# SCH_AGV_genzero_10_ir_array_2024-06-24.net
KiCad netlist of a schematic drawn in EasyEDA
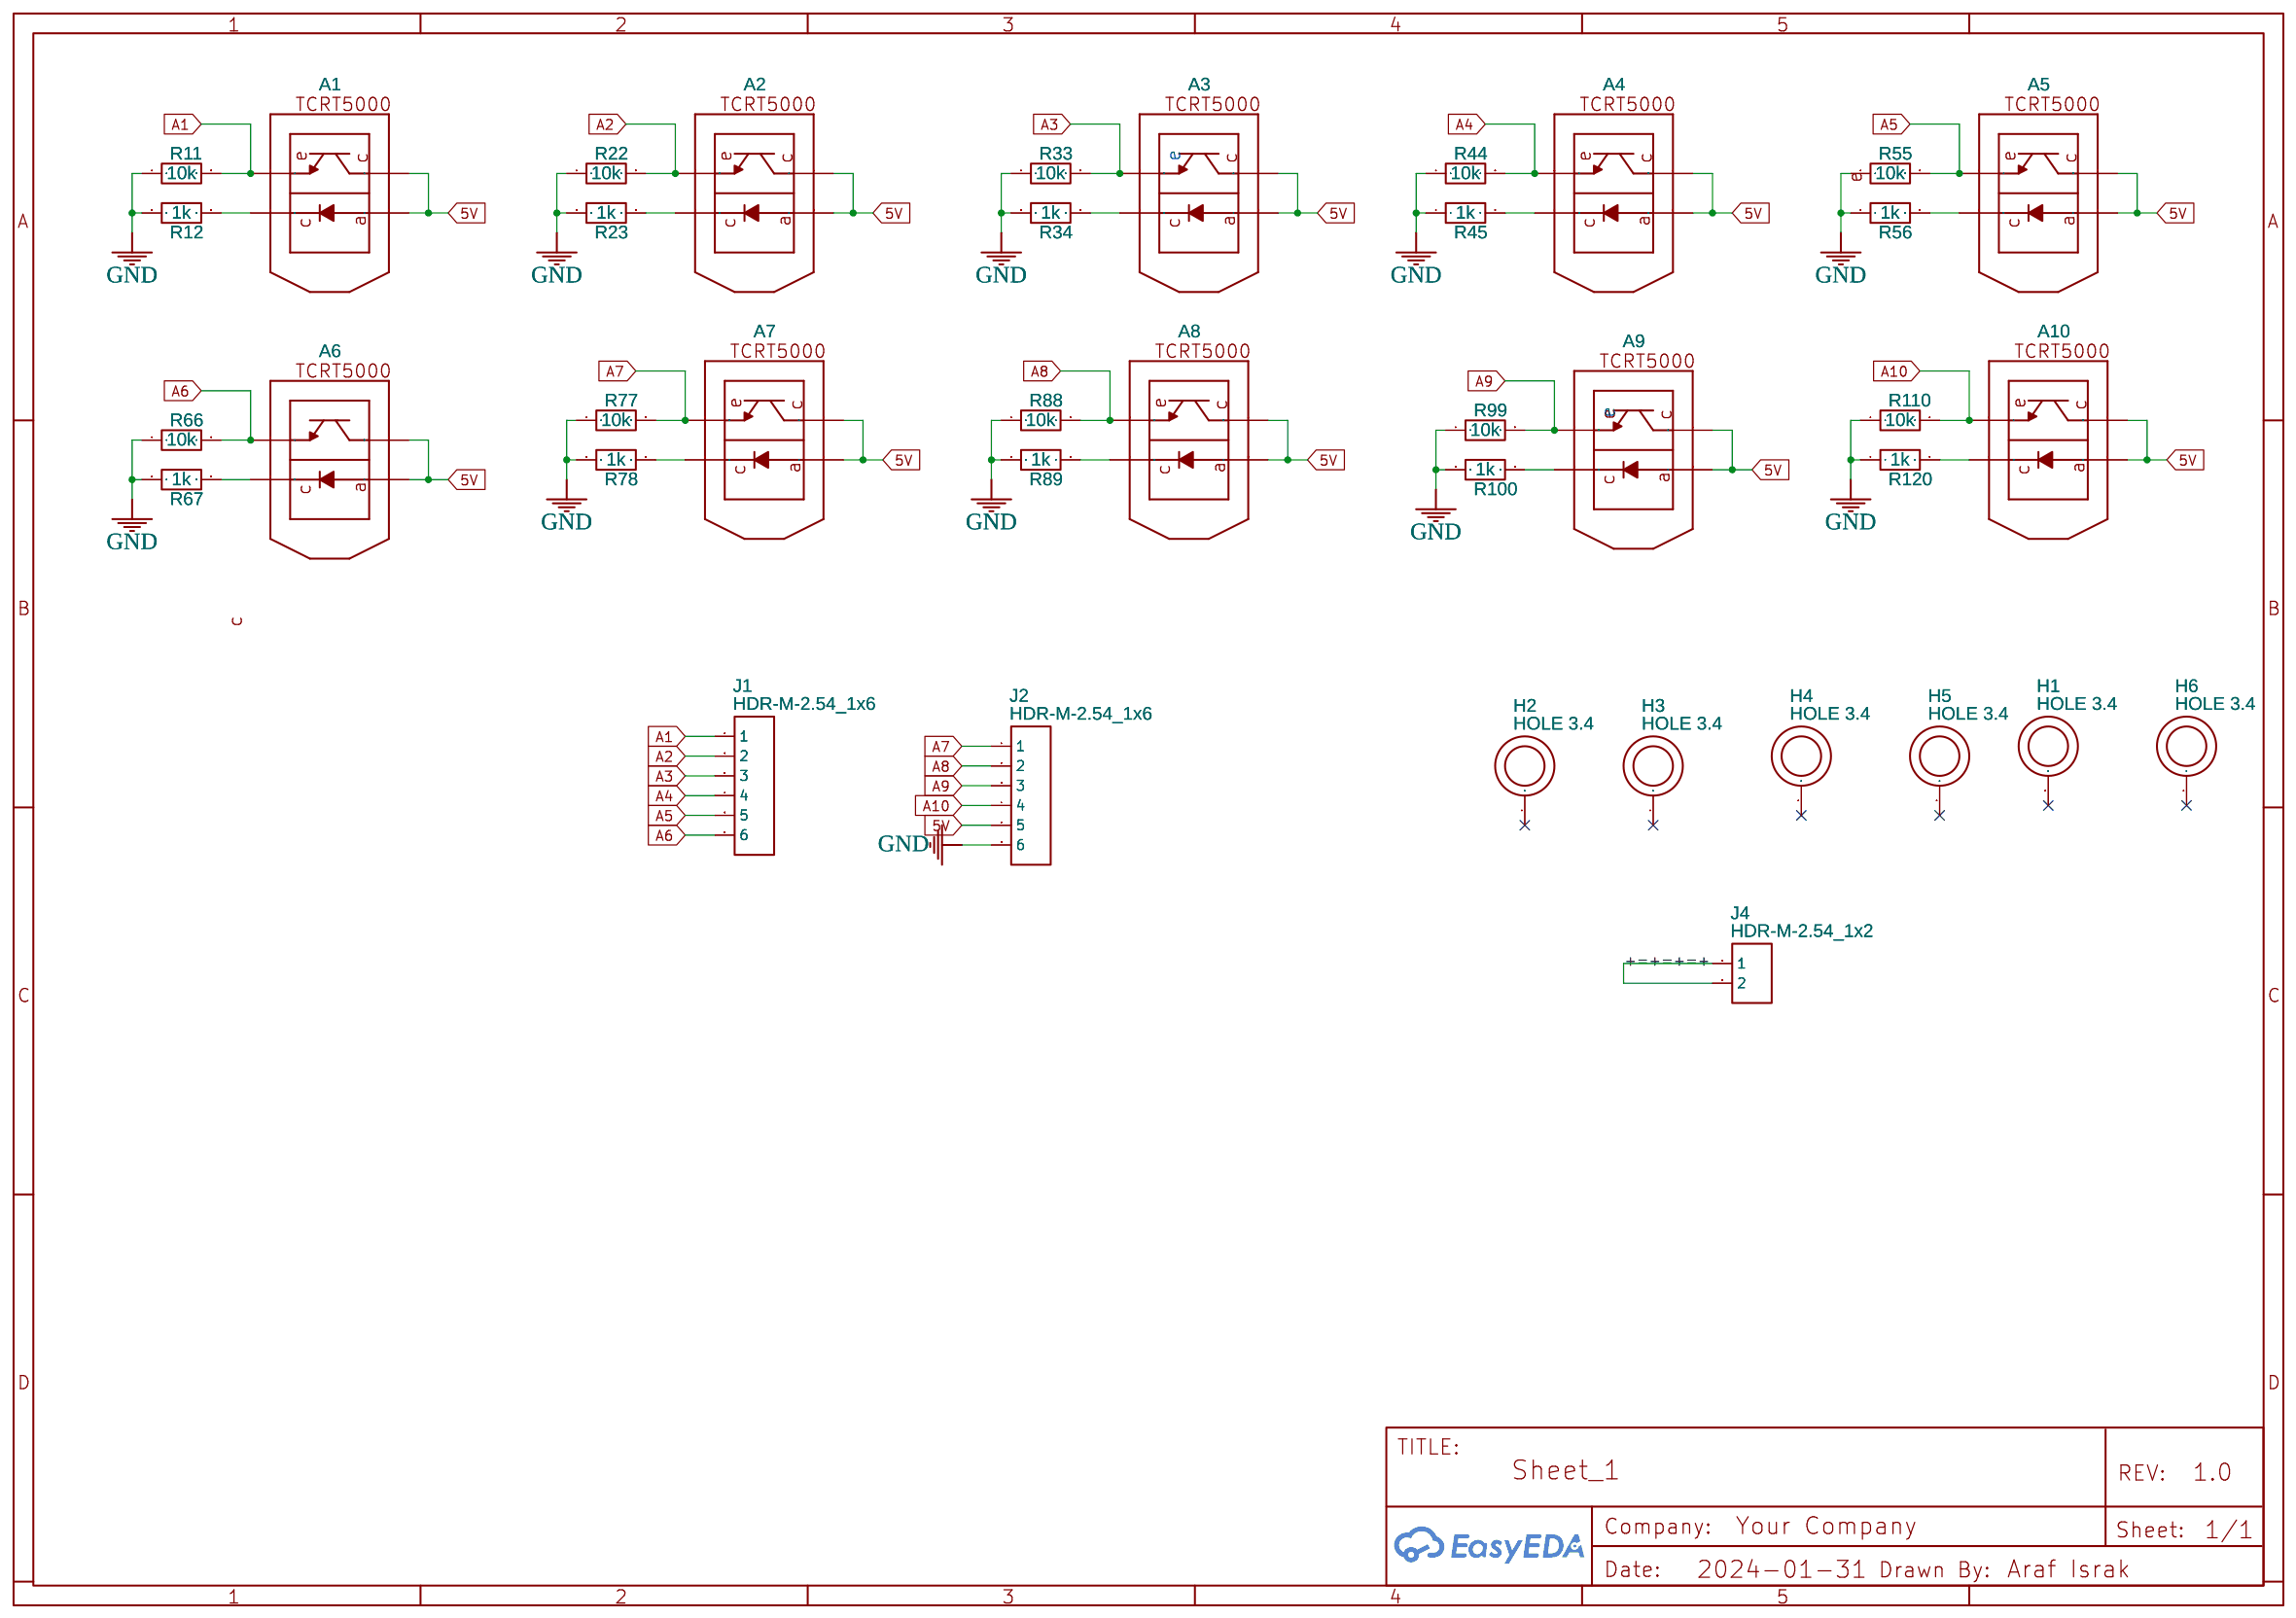
[diagram p0: schematic sheet]

(export (version "E")
  (design (tool "Eeschema 10.0.6"))
  (components
    (comp (ref "A1")
      (value "TCRT5000L")
      (fields (field (name "Manufacturer") "VISHAY(威世)"))
      (libsource (lib "") (part "TCRT5000L"))
    )
    (comp (ref "A2")
      (value "TCRT5000L")
      (fields (field (name "Manufacturer") "VISHAY(威世)"))
      (libsource (lib "") (part "TCRT5000L"))
    )
    (comp (ref "A3")
      (value "TCRT5000L")
      (fields (field (name "Manufacturer") "VISHAY(威世)"))
      (libsource (lib "") (part "TCRT5000L_2"))
    )
    (comp (ref "A4")
      (value "TCRT5000L")
      (fields (field (name "Manufacturer") "VISHAY(威世)"))
      (libsource (lib "") (part "TCRT5000L_1"))
    )
    (comp (ref "A5")
      (value "TCRT5000L")
      (fields (field (name "Manufacturer") "VISHAY(威世)"))
      (libsource (lib "") (part "TCRT5000L_1"))
    )
    (comp (ref "A6")
      (value "TCRT5000L")
      (fields (field (name "Manufacturer") "VISHAY(威世)"))
      (libsource (lib "") (part "TCRT5000L_3"))
    )
    (comp (ref "A7")
      (value "TCRT5000L")
      (fields (field (name "Manufacturer") "VISHAY(威世)"))
      (libsource (lib "") (part "TCRT5000L"))
    )
    (comp (ref "A8")
      (value "TCRT5000L")
      (fields (field (name "Manufacturer") "VISHAY(威世)"))
      (libsource (lib "") (part "TCRT5000L_1"))
    )
    (comp (ref "A9")
      (value "TCRT5000L")
      (fields (field (name "Manufacturer") "VISHAY(威世)"))
      (libsource (lib "") (part "TCRT5000L_4"))
    )
    (comp (ref "A10")
      (value "TCRT5000L")
      (fields (field (name "Manufacturer") "VISHAY(威世)"))
      (libsource (lib "") (part "TCRT5000L_1"))
    )
    (comp (ref "H1") (value "HOLE 3.4") (libsource (lib "") (part "HOLE 3.4")))
    (comp (ref "H2") (value "HOLE 3.4") (libsource (lib "") (part "HOLE 3.4")))
    (comp (ref "H3") (value "HOLE 3.4") (libsource (lib "") (part "HOLE 3.4")))
    (comp (ref "H4") (value "HOLE 3.4") (libsource (lib "") (part "HOLE 3.4")))
    (comp (ref "H5") (value "HOLE 3.4") (libsource (lib "") (part "HOLE 3.4")))
    (comp (ref "H6") (value "HOLE 3.4") (libsource (lib "") (part "HOLE 3.4")))
    (comp (ref "J1") (value "HDR-M-2.54_1x6") (libsource (lib "") (part "HDR-M-2.54_1x6")))
    (comp (ref "J2") (value "HDR-M-2.54_1x6") (libsource (lib "") (part "HDR-M-2.54_1x6")))
    (comp (ref "J4") (value "HDR-M-2.54_1x2") (libsource (lib "") (part "HDR-M-2.54_1x2")))
    (comp (ref "R11")
      (value "10k")
      (fields (field (name "Manufacturer Part") "CF1/6W-10KΩ±5%T52") (field (name "Manufacturer") "华星机电"))
      (libsource (lib "") (part "CF1/6W-10KΩ±5%T52"))
    )
    (comp (ref "R12")
      (value "1k")
      (fields (field (name "Manufacturer Part") "CF1/6W-10KΩ±5%T52") (field (name "Manufacturer") "华星机电"))
      (libsource (lib "") (part "CF1/6W-10KΩ±5%T52"))
    )
    (comp (ref "R22")
      (value "10k")
      (fields (field (name "Manufacturer Part") "CF1/6W-10KΩ±5%T52") (field (name "Manufacturer") "华星机电"))
      (libsource (lib "") (part "CF1/6W-10KΩ±5%T52"))
    )
    (comp (ref "R23")
      (value "1k")
      (fields (field (name "Manufacturer Part") "CF1/6W-10KΩ±5%T52") (field (name "Manufacturer") "华星机电"))
      (libsource (lib "") (part "CF1/6W-10KΩ±5%T52"))
    )
    (comp (ref "R33")
      (value "10k")
      (fields (field (name "Manufacturer Part") "CF1/6W-10KΩ±5%T52") (field (name "Manufacturer") "华星机电"))
      (libsource (lib "") (part "CF1/6W-10KΩ±5%T52"))
    )
    (comp (ref "R34")
      (value "1k")
      (fields (field (name "Manufacturer Part") "CF1/6W-10KΩ±5%T52") (field (name "Manufacturer") "华星机电"))
      (libsource (lib "") (part "CF1/6W-10KΩ±5%T52"))
    )
    (comp (ref "R44")
      (value "10k")
      (fields (field (name "Manufacturer Part") "CF1/6W-10KΩ±5%T52") (field (name "Manufacturer") "华星机电"))
      (libsource (lib "") (part "CF1/6W-10KΩ±5%T52"))
    )
    (comp (ref "R45")
      (value "1k")
      (fields (field (name "Manufacturer Part") "CF1/6W-10KΩ±5%T52") (field (name "Manufacturer") "华星机电"))
      (libsource (lib "") (part "CF1/6W-10KΩ±5%T52"))
    )
    (comp (ref "R55")
      (value "10k")
      (fields (field (name "Manufacturer Part") "CF1/6W-10KΩ±5%T52") (field (name "Manufacturer") "华星机电"))
      (libsource (lib "") (part "CF1/6W-10KΩ±5%T52"))
    )
    (comp (ref "R56")
      (value "1k")
      (fields (field (name "Manufacturer Part") "CF1/6W-10KΩ±5%T52") (field (name "Manufacturer") "华星机电"))
      (libsource (lib "") (part "CF1/6W-10KΩ±5%T52"))
    )
    (comp (ref "R66")
      (value "10k")
      (fields (field (name "Manufacturer Part") "CF1/6W-10KΩ±5%T52") (field (name "Manufacturer") "华星机电"))
      (libsource (lib "") (part "CF1/6W-10KΩ±5%T52"))
    )
    (comp (ref "R67")
      (value "1k")
      (fields (field (name "Manufacturer Part") "CF1/6W-10KΩ±5%T52") (field (name "Manufacturer") "华星机电"))
      (libsource (lib "") (part "CF1/6W-10KΩ±5%T52"))
    )
    (comp (ref "R77")
      (value "10k")
      (fields (field (name "Manufacturer Part") "CF1/6W-10KΩ±5%T52") (field (name "Manufacturer") "华星机电"))
      (libsource (lib "") (part "CF1/6W-10KΩ±5%T52"))
    )
    (comp (ref "R78")
      (value "1k")
      (fields (field (name "Manufacturer Part") "CF1/6W-10KΩ±5%T52") (field (name "Manufacturer") "华星机电"))
      (libsource (lib "") (part "CF1/6W-10KΩ±5%T52"))
    )
    (comp (ref "R88")
      (value "10k")
      (fields (field (name "Manufacturer Part") "CF1/6W-10KΩ±5%T52") (field (name "Manufacturer") "华星机电"))
      (libsource (lib "") (part "CF1/6W-10KΩ±5%T52"))
    )
    (comp (ref "R89")
      (value "1k")
      (fields (field (name "Manufacturer Part") "CF1/6W-10KΩ±5%T52") (field (name "Manufacturer") "华星机电"))
      (libsource (lib "") (part "CF1/6W-10KΩ±5%T52"))
    )
    (comp (ref "R99")
      (value "10k")
      (fields (field (name "Manufacturer Part") "CF1/6W-10KΩ±5%T52") (field (name "Manufacturer") "华星机电"))
      (libsource (lib "") (part "CF1/6W-10KΩ±5%T52"))
    )
    (comp (ref "R100")
      (value "1k")
      (fields (field (name "Manufacturer Part") "CF1/6W-10KΩ±5%T52") (field (name "Manufacturer") "华星机电"))
      (libsource (lib "") (part "CF1/6W-10KΩ±5%T52"))
    )
    (comp (ref "R110")
      (value "10k")
      (fields (field (name "Manufacturer Part") "CF1/6W-10KΩ±5%T52") (field (name "Manufacturer") "华星机电"))
      (libsource (lib "") (part "CF1/6W-10KΩ±5%T52"))
    )
    (comp (ref "R120")
      (value "1k")
      (fields (field (name "Manufacturer Part") "CF1/6W-10KΩ±5%T52") (field (name "Manufacturer") "华星机电"))
      (libsource (lib "") (part "CF1/6W-10KΩ±5%T52"))
    )
  )
  (nets
    (net (code "1") (name "/+=+=+=+") (class "Default")
      (node (ref "J4") (pin "1") (pinfunction "1_1") (pintype "unspecified"))
      (node (ref "J4") (pin "2") (pinfunction "2_2") (pintype "unspecified"))
    )
    (net (code "2") (name "5V") (class "Default")
      (node (ref "A1") (pin "1") (pinfunction "C_1") (pintype "unspecified"))
      (node (ref "A1") (pin "3") (pinfunction "A_3") (pintype "unspecified"))
      (node (ref "A10") (pin "1") (pinfunction "C_1") (pintype "unspecified"))
      (node (ref "A10") (pin "3") (pinfunction "A_3") (pintype "unspecified"))
      (node (ref "A2") (pin "1") (pinfunction "C_1") (pintype "unspecified"))
      (node (ref "A2") (pin "3") (pinfunction "A_3") (pintype "unspecified"))
      (node (ref "A3") (pin "1") (pinfunction "C_1") (pintype "unspecified"))
      (node (ref "A3") (pin "3") (pinfunction "A_3") (pintype "unspecified"))
      (node (ref "A4") (pin "1") (pinfunction "C_1") (pintype "unspecified"))
      (node (ref "A4") (pin "3") (pinfunction "A_3") (pintype "unspecified"))
      (node (ref "A5") (pin "1") (pinfunction "C_1") (pintype "unspecified"))
      (node (ref "A5") (pin "3") (pinfunction "A_3") (pintype "unspecified"))
      (node (ref "A6") (pin "1") (pinfunction "C_1") (pintype "unspecified"))
      (node (ref "A6") (pin "3") (pinfunction "A_3") (pintype "unspecified"))
      (node (ref "A7") (pin "1") (pinfunction "C_1") (pintype "unspecified"))
      (node (ref "A7") (pin "3") (pinfunction "A_3") (pintype "unspecified"))
      (node (ref "A8") (pin "1") (pinfunction "C_1") (pintype "unspecified"))
      (node (ref "A8") (pin "3") (pinfunction "A_3") (pintype "unspecified"))
      (node (ref "A9") (pin "1") (pinfunction "C_1") (pintype "unspecified"))
      (node (ref "A9") (pin "3") (pinfunction "A_3") (pintype "unspecified"))
      (node (ref "J2") (pin "5") (pinfunction "5_5") (pintype "input"))
    )
    (net (code "3") (name "A1") (class "Default")
      (node (ref "A1") (pin "2") (pinfunction "E_2") (pintype "unspecified"))
      (node (ref "J1") (pin "1") (pinfunction "1_1") (pintype "input"))
      (node (ref "R11") (pin "2") (pinfunction "2_2") (pintype "unspecified"))
    )
    (net (code "4") (name "A2") (class "Default")
      (node (ref "A2") (pin "2") (pinfunction "E_2") (pintype "unspecified"))
      (node (ref "J1") (pin "2") (pinfunction "2_2") (pintype "input"))
      (node (ref "R22") (pin "2") (pinfunction "2_2") (pintype "unspecified"))
    )
    (net (code "5") (name "A3") (class "Default")
      (node (ref "A3") (pin "2") (pinfunction "E_2") (pintype "unspecified"))
      (node (ref "J1") (pin "3") (pinfunction "3_3") (pintype "input"))
      (node (ref "R33") (pin "2") (pinfunction "2_2") (pintype "unspecified"))
    )
    (net (code "6") (name "A4") (class "Default")
      (node (ref "A4") (pin "2") (pinfunction "E_2") (pintype "unspecified"))
      (node (ref "J1") (pin "4") (pinfunction "4_4") (pintype "input"))
      (node (ref "R44") (pin "2") (pinfunction "2_2") (pintype "unspecified"))
    )
    (net (code "7") (name "A5") (class "Default")
      (node (ref "A5") (pin "2") (pinfunction "E_2") (pintype "unspecified"))
      (node (ref "J1") (pin "5") (pinfunction "5_5") (pintype "input"))
      (node (ref "R55") (pin "2") (pinfunction "2_2") (pintype "unspecified"))
    )
    (net (code "8") (name "A6") (class "Default")
      (node (ref "A6") (pin "2") (pinfunction "E_2") (pintype "unspecified"))
      (node (ref "J1") (pin "6") (pinfunction "6_6") (pintype "input"))
      (node (ref "R66") (pin "2") (pinfunction "2_2") (pintype "unspecified"))
    )
    (net (code "9") (name "A7") (class "Default")
      (node (ref "A7") (pin "2") (pinfunction "E_2") (pintype "unspecified"))
      (node (ref "J2") (pin "1") (pinfunction "1_1") (pintype "input"))
      (node (ref "R77") (pin "2") (pinfunction "2_2") (pintype "unspecified"))
    )
    (net (code "10") (name "A8") (class "Default")
      (node (ref "A8") (pin "2") (pinfunction "E_2") (pintype "unspecified"))
      (node (ref "J2") (pin "2") (pinfunction "2_2") (pintype "input"))
      (node (ref "R88") (pin "2") (pinfunction "2_2") (pintype "unspecified"))
    )
    (net (code "11") (name "A9") (class "Default")
      (node (ref "A9") (pin "2") (pinfunction "E_2") (pintype "unspecified"))
      (node (ref "J2") (pin "3") (pinfunction "3_3") (pintype "input"))
      (node (ref "R99") (pin "2") (pinfunction "2_2") (pintype "unspecified"))
    )
    (net (code "12") (name "A10") (class "Default")
      (node (ref "A10") (pin "2") (pinfunction "E_2") (pintype "unspecified"))
      (node (ref "J2") (pin "4") (pinfunction "4_4") (pintype "input"))
      (node (ref "R110") (pin "2") (pinfunction "2_2") (pintype "unspecified"))
    )
    (net (code "13") (name "GND") (class "Default")
      (node (ref "J2") (pin "6") (pinfunction "6_6") (pintype "input"))
      (node (ref "R100") (pin "1") (pinfunction "1_1") (pintype "unspecified"))
      (node (ref "R11") (pin "1") (pinfunction "1_1") (pintype "unspecified"))
      (node (ref "R110") (pin "1") (pinfunction "1_1") (pintype "unspecified"))
      (node (ref "R12") (pin "1") (pinfunction "1_1") (pintype "unspecified"))
      (node (ref "R120") (pin "1") (pinfunction "1_1") (pintype "unspecified"))
      (node (ref "R22") (pin "1") (pinfunction "1_1") (pintype "unspecified"))
      (node (ref "R23") (pin "1") (pinfunction "1_1") (pintype "unspecified"))
      (node (ref "R33") (pin "1") (pinfunction "1_1") (pintype "unspecified"))
      (node (ref "R34") (pin "1") (pinfunction "1_1") (pintype "unspecified"))
      (node (ref "R44") (pin "1") (pinfunction "1_1") (pintype "unspecified"))
      (node (ref "R45") (pin "1") (pinfunction "1_1") (pintype "unspecified"))
      (node (ref "R55") (pin "1") (pinfunction "1_1") (pintype "unspecified"))
      (node (ref "R56") (pin "1") (pinfunction "1_1") (pintype "unspecified"))
      (node (ref "R66") (pin "1") (pinfunction "1_1") (pintype "unspecified"))
      (node (ref "R67") (pin "1") (pinfunction "1_1") (pintype "unspecified"))
      (node (ref "R77") (pin "1") (pinfunction "1_1") (pintype "unspecified"))
      (node (ref "R78") (pin "1") (pinfunction "1_1") (pintype "unspecified"))
      (node (ref "R88") (pin "1") (pinfunction "1_1") (pintype "unspecified"))
      (node (ref "R89") (pin "1") (pinfunction "1_1") (pintype "unspecified"))
      (node (ref "R99") (pin "1") (pinfunction "1_1") (pintype "unspecified"))
    )
    (net (code "14") (name "Net-(A1-C-Pad4)") (class "Default")
      (node (ref "A1") (pin "4") (pinfunction "C_4") (pintype "unspecified"))
      (node (ref "R12") (pin "2") (pinfunction "2_2") (pintype "unspecified"))
    )
    (net (code "15") (name "Net-(A2-C-Pad4)") (class "Default")
      (node (ref "A2") (pin "4") (pinfunction "C_4") (pintype "unspecified"))
      (node (ref "R23") (pin "2") (pinfunction "2_2") (pintype "unspecified"))
    )
    (net (code "16") (name "Net-(A3-C-Pad4)") (class "Default")
      (node (ref "A3") (pin "4") (pinfunction "C_4") (pintype "unspecified"))
      (node (ref "R34") (pin "2") (pinfunction "2_2") (pintype "unspecified"))
    )
    (net (code "17") (name "Net-(A4-C-Pad4)") (class "Default")
      (node (ref "A4") (pin "4") (pinfunction "C_4") (pintype "unspecified"))
      (node (ref "R45") (pin "2") (pinfunction "2_2") (pintype "unspecified"))
    )
    (net (code "18") (name "Net-(A5-C-Pad4)") (class "Default")
      (node (ref "A5") (pin "4") (pinfunction "C_4") (pintype "unspecified"))
      (node (ref "R56") (pin "2") (pinfunction "2_2") (pintype "unspecified"))
    )
    (net (code "19") (name "Net-(A6-C-Pad4)") (class "Default")
      (node (ref "A6") (pin "4") (pinfunction "C_4") (pintype "unspecified"))
      (node (ref "R67") (pin "2") (pinfunction "2_2") (pintype "unspecified"))
    )
    (net (code "20") (name "Net-(A7-C-Pad4)") (class "Default")
      (node (ref "A7") (pin "4") (pinfunction "C_4") (pintype "unspecified"))
      (node (ref "R78") (pin "2") (pinfunction "2_2") (pintype "unspecified"))
    )
    (net (code "21") (name "Net-(A8-C-Pad4)") (class "Default")
      (node (ref "A8") (pin "4") (pinfunction "C_4") (pintype "unspecified"))
      (node (ref "R89") (pin "2") (pinfunction "2_2") (pintype "unspecified"))
    )
    (net (code "22") (name "Net-(A9-C-Pad4)") (class "Default")
      (node (ref "A9") (pin "4") (pinfunction "C_4") (pintype "unspecified"))
      (node (ref "R100") (pin "2") (pinfunction "2_2") (pintype "unspecified"))
    )
    (net (code "23") (name "Net-(A10-C-Pad4)") (class "Default")
      (node (ref "A10") (pin "4") (pinfunction "C_4") (pintype "unspecified"))
      (node (ref "R120") (pin "2") (pinfunction "2_2") (pintype "unspecified"))
    )
    (net (code "24") (name "unconnected-(H1-Pad1)") (class "Default")
      (node (ref "H1") (pin "1") (pinfunction "1_1") (pintype "unspecified+no_connect"))
    )
    (net (code "25") (name "unconnected-(H2-Pad1)") (class "Default")
      (node (ref "H2") (pin "1") (pinfunction "1_1") (pintype "unspecified+no_connect"))
    )
    (net (code "26") (name "unconnected-(H3-Pad1)") (class "Default")
      (node (ref "H3") (pin "1") (pinfunction "1_1") (pintype "unspecified+no_connect"))
    )
    (net (code "27") (name "unconnected-(H4-Pad1)") (class "Default")
      (node (ref "H4") (pin "1") (pinfunction "1_1") (pintype "unspecified+no_connect"))
    )
    (net (code "28") (name "unconnected-(H5-Pad1)") (class "Default")
      (node (ref "H5") (pin "1") (pinfunction "1_1") (pintype "unspecified+no_connect"))
    )
    (net (code "29") (name "unconnected-(H6-Pad1)") (class "Default")
      (node (ref "H6") (pin "1") (pinfunction "1_1") (pintype "unspecified+no_connect"))
    )
  )
)
